# Board.net
KiCad netlist of a schematic drawn in EAGLE
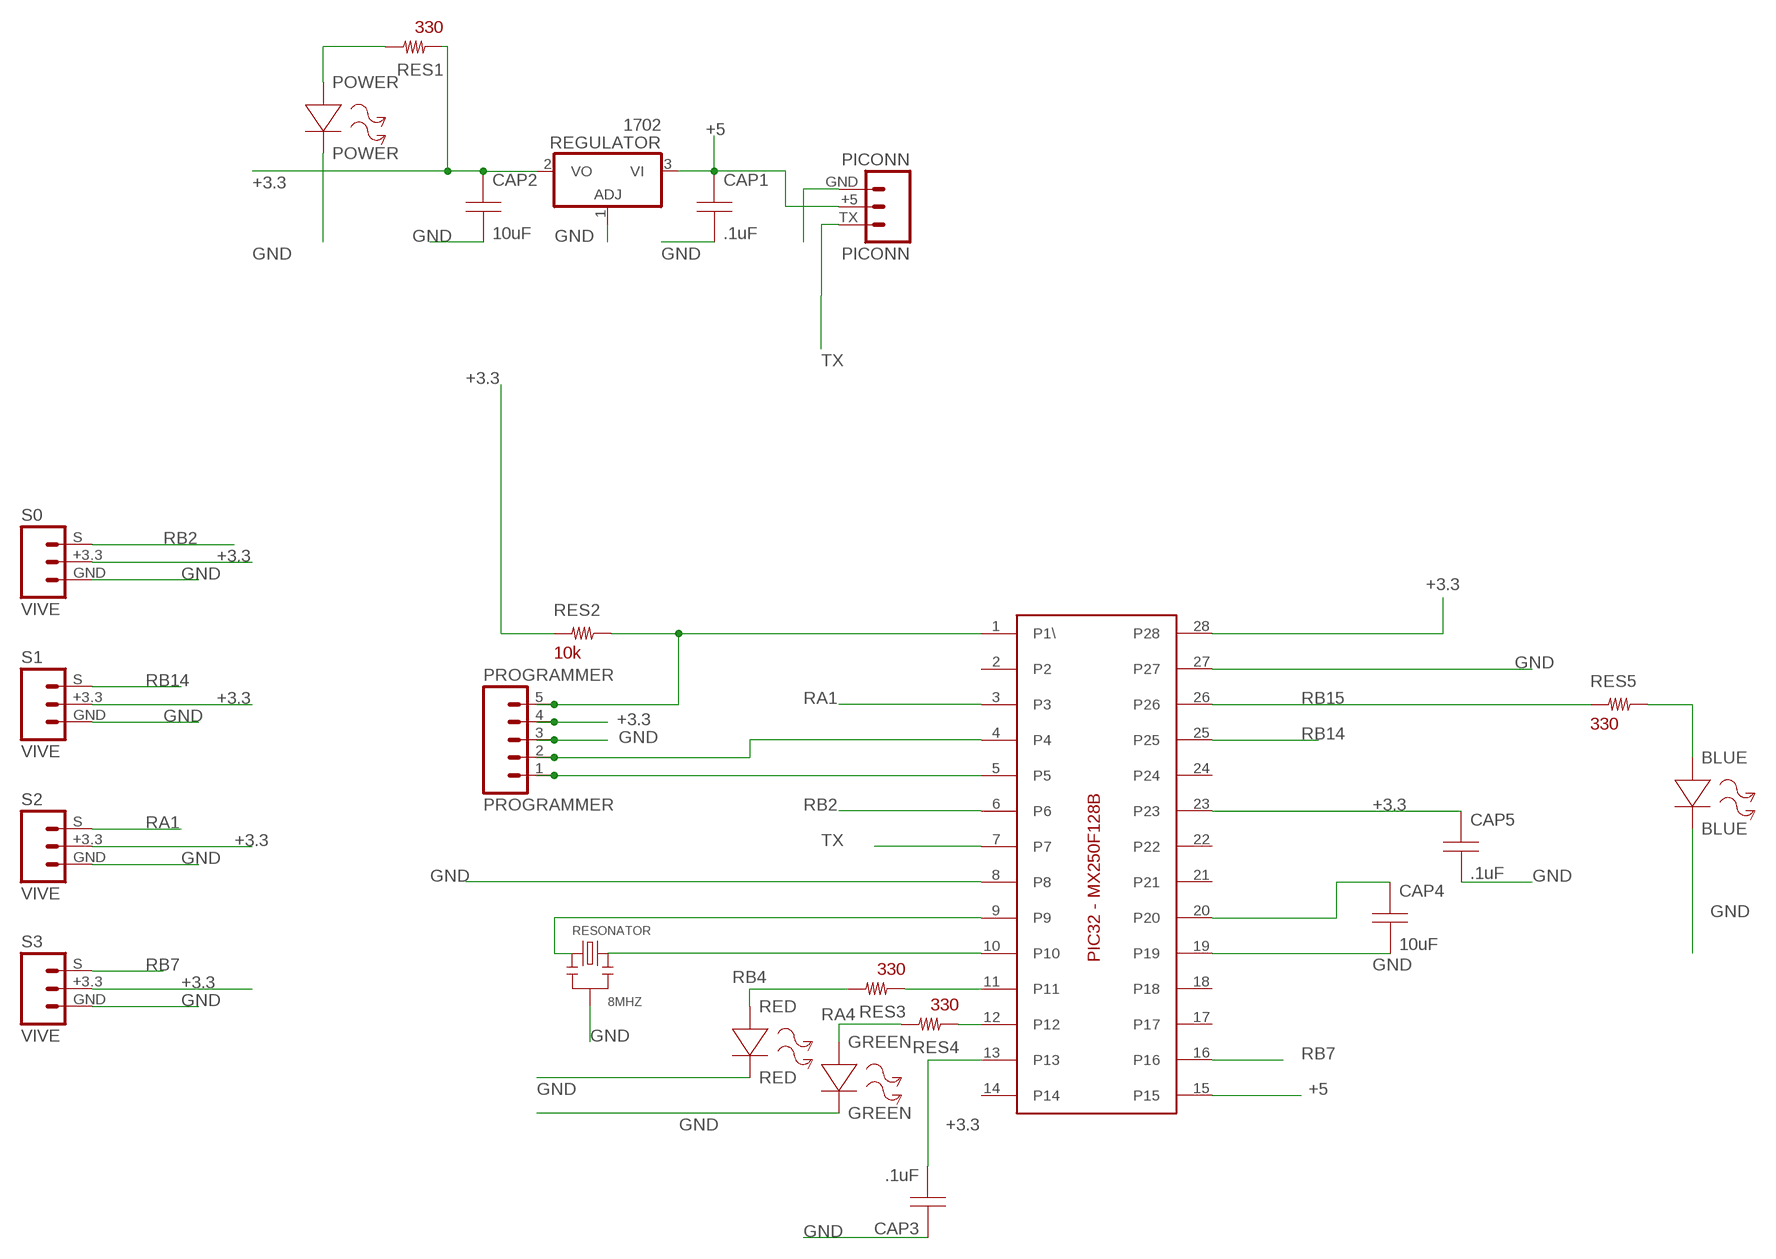
[diagram p0: schematic, sheet 1]

(export (version "E")
  (design (tool "Eeschema 10.0.6"))
  (components
    (comp (ref "1702")
      (value "REGULATOR")
      (footprint "eagle-import:REGULATOR3P")
      (libsource (lib "eagle-import") (part "REGULATOR"))
    )
    (comp (ref "BLUE")
      (value "BLUE")
      (footprint "eagle-import:L0603")
      (libsource (lib "eagle-import") (part "LEDL0603"))
    )
    (comp (ref "CAP1")
      (value ".1uF")
      (footprint "eagle-import:C0603")
      (libsource (lib "eagle-import") (part "CAPACITOR0603"))
    )
    (comp (ref "CAP2")
      (value "10uF")
      (footprint "eagle-import:C0805")
      (libsource (lib "eagle-import") (part "CAPACITOR0805"))
    )
    (comp (ref "CAP3")
      (value ".1uF")
      (footprint "eagle-import:C0603")
      (libsource (lib "eagle-import") (part "CAPACITOR0603"))
    )
    (comp (ref "CAP4")
      (value "10uF")
      (footprint "eagle-import:C0805")
      (libsource (lib "eagle-import") (part "CAPACITOR0805"))
    )
    (comp (ref "CAP5")
      (value ".1uF")
      (footprint "eagle-import:C0603")
      (libsource (lib "eagle-import") (part "CAPACITOR0603"))
    )
    (comp (ref "GREEN")
      (value "GREEN")
      (footprint "eagle-import:L0603")
      (libsource (lib "eagle-import") (part "LEDL0603"))
    )
    (comp (ref "PIC")
      (value "PIC32-MX250F128BSSOP")
      (footprint "eagle-import:PIC32SSOP")
      (libsource (lib "eagle-import") (part "PIC32-MX250F128BSSOP"))
    )
    (comp (ref "PICONN")
      (value "PICONN")
      (footprint "eagle-import:PICONN")
      (libsource (lib "eagle-import") (part "PICONN"))
    )
    (comp (ref "POWER")
      (value "POWER")
      (footprint "eagle-import:L0603")
      (libsource (lib "eagle-import") (part "LEDL0603"))
    )
    (comp (ref "PROGRAMMER")
      (value "PROGRAMMER")
      (footprint "eagle-import:PROGRAMMER5P")
      (libsource (lib "eagle-import") (part "PROGRAMMERPTH"))
    )
    (comp (ref "RED")
      (value "RED")
      (footprint "eagle-import:L0603")
      (libsource (lib "eagle-import") (part "LEDL0603"))
    )
    (comp (ref "RES1")
      (value "330")
      (footprint "eagle-import:R0603")
      (libsource (lib "eagle-import") (part "RESISTORR0603"))
    )
    (comp (ref "RES2")
      (value "10k")
      (footprint "eagle-import:R0603")
      (libsource (lib "eagle-import") (part "RESISTORR0603"))
    )
    (comp (ref "RES3")
      (value "330")
      (footprint "eagle-import:R0603")
      (libsource (lib "eagle-import") (part "RESISTORR0603"))
    )
    (comp (ref "RES4")
      (value "330")
      (footprint "eagle-import:R0603")
      (libsource (lib "eagle-import") (part "RESISTORR0603"))
    )
    (comp (ref "RES5")
      (value "330")
      (footprint "eagle-import:R0603")
      (libsource (lib "eagle-import") (part "RESISTORR0603"))
    )
    (comp (ref "RESONATOR")
      (value "8MHZ")
      (footprint "eagle-import:OSC")
      (libsource (lib "eagle-import") (part "OSCILATOROSC"))
    )
    (comp (ref "S0")
      (value "VIVE")
      (footprint "eagle-import:VIVE")
      (libsource (lib "eagle-import") (part "VIVE"))
    )
    (comp (ref "S1")
      (value "VIVE")
      (footprint "eagle-import:VIVE")
      (libsource (lib "eagle-import") (part "VIVE"))
    )
    (comp (ref "S2")
      (value "VIVE")
      (footprint "eagle-import:VIVE")
      (libsource (lib "eagle-import") (part "VIVE"))
    )
    (comp (ref "S3")
      (value "VIVE")
      (footprint "eagle-import:VIVE")
      (libsource (lib "eagle-import") (part "VIVE"))
    )
  )
  (nets
    (net (code "1") (name "/+3.3") (class "Default")
      (node (ref "1702") (pin "2") (pinfunction "VO_2") (pintype "passive"))
      (node (ref "CAP2") (pin "1") (pinfunction "A_1") (pintype "passive"))
      (node (ref "CAP3") (pin "2") (pinfunction "B_2") (pintype "passive"))
      (node (ref "CAP5") (pin "1") (pinfunction "A_1") (pintype "passive"))
      (node (ref "PIC") (pin "13") (pinfunction "P13_13") (pintype "bidirectional"))
      (node (ref "PIC") (pin "23") (pinfunction "P23_23") (pintype "bidirectional"))
      (node (ref "PIC") (pin "28") (pinfunction "P28_28") (pintype "bidirectional"))
      (node (ref "PROGRAMMER") (pin "4") (pinfunction "4_4") (pintype "passive"))
      (node (ref "RES1") (pin "1") (pinfunction "P$1_1") (pintype "bidirectional"))
      (node (ref "RES2") (pin "1") (pinfunction "P$1_1") (pintype "bidirectional"))
      (node (ref "S0") (pin "+3.3") (pinfunction "+3.3_+3.3") (pintype "passive"))
      (node (ref "S1") (pin "+3.3") (pinfunction "+3.3_+3.3") (pintype "passive"))
      (node (ref "S2") (pin "+3.3") (pinfunction "+3.3_+3.3") (pintype "passive"))
      (node (ref "S3") (pin "+3.3") (pinfunction "+3.3_+3.3") (pintype "passive"))
    )
    (net (code "2") (name "/+5") (class "Default")
      (node (ref "1702") (pin "3") (pinfunction "VI_3") (pintype "input"))
      (node (ref "CAP1") (pin "1") (pinfunction "A_1") (pintype "passive"))
      (node (ref "PIC") (pin "15") (pinfunction "P15_15") (pintype "bidirectional"))
      (node (ref "PICONN") (pin "+5") (pinfunction "+5_+5") (pintype "passive"))
    )
    (net (code "3") (name "/GND") (class "Default")
      (node (ref "1702") (pin "1") (pinfunction "ADJ_1") (pintype "input"))
      (node (ref "BLUE") (pin "2") (pinfunction "-_2") (pintype "passive"))
      (node (ref "CAP1") (pin "2") (pinfunction "B_2") (pintype "passive"))
      (node (ref "CAP2") (pin "2") (pinfunction "B_2") (pintype "passive"))
      (node (ref "CAP3") (pin "1") (pinfunction "A_1") (pintype "passive"))
      (node (ref "CAP4") (pin "2") (pinfunction "B_2") (pintype "passive"))
      (node (ref "CAP5") (pin "2") (pinfunction "B_2") (pintype "passive"))
      (node (ref "GREEN") (pin "2") (pinfunction "-_2") (pintype "passive"))
      (node (ref "PIC") (pin "19") (pinfunction "P19_19") (pintype "bidirectional"))
      (node (ref "PIC") (pin "27") (pinfunction "P27_27") (pintype "bidirectional"))
      (node (ref "PIC") (pin "8") (pinfunction "P8_8") (pintype "bidirectional"))
      (node (ref "PICONN") (pin "GND") (pinfunction "GND_GND") (pintype "passive"))
      (node (ref "POWER") (pin "2") (pinfunction "-_2") (pintype "passive"))
      (node (ref "PROGRAMMER") (pin "3") (pinfunction "3_3") (pintype "passive"))
      (node (ref "RED") (pin "2") (pinfunction "-_2") (pintype "passive"))
      (node (ref "RESONATOR") (pin "2") (pinfunction "2_2") (pintype "passive"))
      (node (ref "S0") (pin "GND") (pinfunction "GND_GND") (pintype "passive"))
      (node (ref "S1") (pin "GND") (pinfunction "GND_GND") (pintype "passive"))
      (node (ref "S2") (pin "GND") (pinfunction "GND_GND") (pintype "passive"))
      (node (ref "S3") (pin "GND") (pinfunction "GND_GND") (pintype "passive"))
    )
    (net (code "4") (name "/RA1") (class "Default")
      (node (ref "PIC") (pin "3") (pinfunction "P3_3") (pintype "bidirectional"))
      (node (ref "S2") (pin "S") (pinfunction "S_S") (pintype "passive"))
    )
    (net (code "5") (name "/RA4") (class "Default")
      (node (ref "GREEN") (pin "1") (pinfunction "+_1") (pintype "passive"))
      (node (ref "RES4") (pin "2") (pinfunction "P$2_2") (pintype "bidirectional"))
    )
    (net (code "6") (name "/RB2") (class "Default")
      (node (ref "PIC") (pin "6") (pinfunction "P6_6") (pintype "bidirectional"))
      (node (ref "S0") (pin "S") (pinfunction "S_S") (pintype "passive"))
    )
    (net (code "7") (name "/RB4") (class "Default")
      (node (ref "RED") (pin "1") (pinfunction "+_1") (pintype "passive"))
      (node (ref "RES3") (pin "2") (pinfunction "P$2_2") (pintype "bidirectional"))
    )
    (net (code "8") (name "/RB7") (class "Default")
      (node (ref "PIC") (pin "16") (pinfunction "P16_16") (pintype "bidirectional"))
      (node (ref "S3") (pin "S") (pinfunction "S_S") (pintype "passive"))
    )
    (net (code "9") (name "/RB14") (class "Default")
      (node (ref "PIC") (pin "25") (pinfunction "P25_25") (pintype "bidirectional"))
      (node (ref "S1") (pin "S") (pinfunction "S_S") (pintype "passive"))
    )
    (net (code "10") (name "/RB15") (class "Default")
      (node (ref "PIC") (pin "26") (pinfunction "P26_26") (pintype "bidirectional"))
      (node (ref "RES5") (pin "1") (pinfunction "P$1_1") (pintype "bidirectional"))
    )
    (net (code "11") (name "/TX") (class "Default")
      (node (ref "PIC") (pin "7") (pinfunction "P7_7") (pintype "bidirectional"))
      (node (ref "PICONN") (pin "TX") (pinfunction "TX_TX") (pintype "passive"))
    )
    (net (code "12") (name "Net-(BLUE-+)") (class "Default")
      (node (ref "BLUE") (pin "1") (pinfunction "+_1") (pintype "passive"))
      (node (ref "RES5") (pin "2") (pinfunction "P$2_2") (pintype "bidirectional"))
    )
    (net (code "13") (name "Net-(CAP4-A)") (class "Default")
      (node (ref "CAP4") (pin "1") (pinfunction "A_1") (pintype "passive"))
      (node (ref "PIC") (pin "20") (pinfunction "P20_20") (pintype "bidirectional"))
    )
    (net (code "14") (name "Net-(PIC-P1\\)") (class "Default")
      (node (ref "PIC") (pin "1") (pinfunction "P1\\_1") (pintype "bidirectional"))
      (node (ref "PROGRAMMER") (pin "5") (pinfunction "5_5") (pintype "passive"))
      (node (ref "RES2") (pin "2") (pinfunction "P$2_2") (pintype "bidirectional"))
    )
    (net (code "15") (name "Net-(PIC-P4)") (class "Default")
      (node (ref "PIC") (pin "4") (pinfunction "P4_4") (pintype "bidirectional"))
      (node (ref "PROGRAMMER") (pin "2") (pinfunction "2_2") (pintype "passive"))
    )
    (net (code "16") (name "Net-(PIC-P5)") (class "Default")
      (node (ref "PIC") (pin "5") (pinfunction "P5_5") (pintype "bidirectional"))
      (node (ref "PROGRAMMER") (pin "1") (pinfunction "1_1") (pintype "passive"))
    )
    (net (code "17") (name "Net-(PIC-P9)") (class "Default")
      (node (ref "PIC") (pin "9") (pinfunction "P9_9") (pintype "bidirectional"))
      (node (ref "RESONATOR") (pin "1") (pinfunction "1_1") (pintype "passive"))
    )
    (net (code "18") (name "Net-(PIC-P10)") (class "Default")
      (node (ref "PIC") (pin "10") (pinfunction "P10_10") (pintype "bidirectional"))
      (node (ref "RESONATOR") (pin "3") (pinfunction "3_3") (pintype "passive"))
    )
    (net (code "19") (name "Net-(PIC-P11)") (class "Default")
      (node (ref "PIC") (pin "11") (pinfunction "P11_11") (pintype "bidirectional"))
      (node (ref "RES3") (pin "1") (pinfunction "P$1_1") (pintype "bidirectional"))
    )
    (net (code "20") (name "Net-(PIC-P12)") (class "Default")
      (node (ref "PIC") (pin "12") (pinfunction "P12_12") (pintype "bidirectional"))
      (node (ref "RES4") (pin "1") (pinfunction "P$1_1") (pintype "bidirectional"))
    )
    (net (code "21") (name "Net-(POWER-+)") (class "Default")
      (node (ref "POWER") (pin "1") (pinfunction "+_1") (pintype "passive"))
      (node (ref "RES1") (pin "2") (pinfunction "P$2_2") (pintype "bidirectional"))
    )
    (net (code "22") (name "unconnected-(PIC-P2-Pad2)") (class "Default")
      (node (ref "PIC") (pin "2") (pinfunction "P2_2") (pintype "bidirectional"))
    )
    (net (code "23") (name "unconnected-(PIC-P14-Pad14)") (class "Default")
      (node (ref "PIC") (pin "14") (pinfunction "P14_14") (pintype "bidirectional"))
    )
    (net (code "24") (name "unconnected-(PIC-P17-Pad17)") (class "Default")
      (node (ref "PIC") (pin "17") (pinfunction "P17_17") (pintype "bidirectional"))
    )
    (net (code "25") (name "unconnected-(PIC-P18-Pad18)") (class "Default")
      (node (ref "PIC") (pin "18") (pinfunction "P18_18") (pintype "bidirectional"))
    )
    (net (code "26") (name "unconnected-(PIC-P21-Pad21)") (class "Default")
      (node (ref "PIC") (pin "21") (pinfunction "P21_21") (pintype "bidirectional"))
    )
    (net (code "27") (name "unconnected-(PIC-P22-Pad22)") (class "Default")
      (node (ref "PIC") (pin "22") (pinfunction "P22_22") (pintype "bidirectional"))
    )
    (net (code "28") (name "unconnected-(PIC-P24-Pad24)") (class "Default")
      (node (ref "PIC") (pin "24") (pinfunction "P24_24") (pintype "bidirectional"))
    )
  )
)
